# TPA6132A2RTER.net
KiCad netlist of a schematic drawn in EAGLE
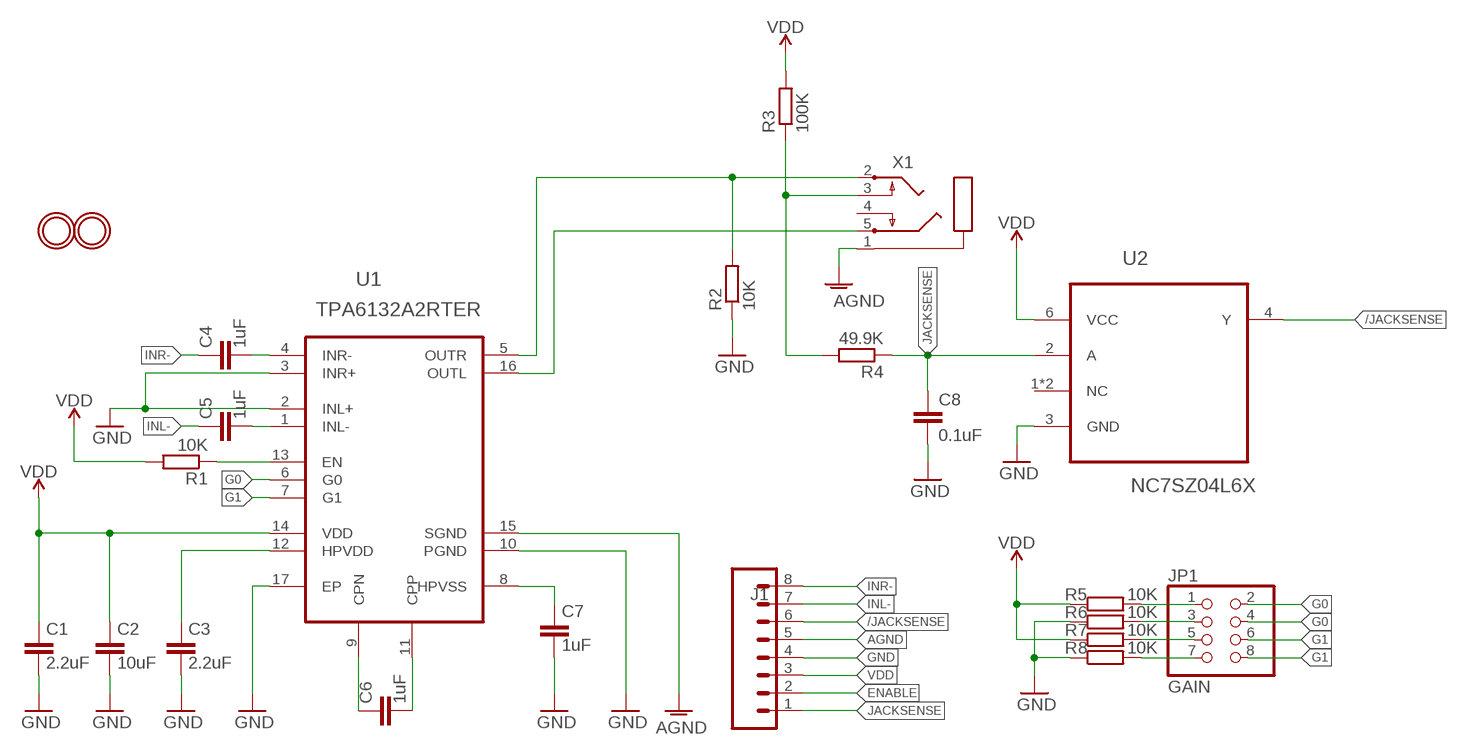
[diagram p0: schematic, sheet 1]

(export (version "E")
  (design (tool "Eeschema 10.0.6"))
  (components
    (comp (ref "C1")
      (value "2.2uF")
      (footprint "eagle-import:C0402K")
      (libsource (lib "eagle-import") (part "C-EUC0402K"))
    )
    (comp (ref "C2")
      (value "10uF")
      (footprint "eagle-import:C0402K")
      (libsource (lib "eagle-import") (part "C-EUC0402K"))
    )
    (comp (ref "C3")
      (value "2.2uF")
      (footprint "eagle-import:C0402K")
      (libsource (lib "eagle-import") (part "C-EUC0402K"))
    )
    (comp (ref "C4")
      (value "1uF")
      (footprint "eagle-import:C0402K")
      (libsource (lib "eagle-import") (part "C-EUC0402K"))
    )
    (comp (ref "C5")
      (value "1uF")
      (footprint "eagle-import:C0402K")
      (libsource (lib "eagle-import") (part "C-EUC0402K"))
    )
    (comp (ref "C6")
      (value "1uF")
      (footprint "eagle-import:C0402K")
      (libsource (lib "eagle-import") (part "C-EUC0402K"))
    )
    (comp (ref "C7")
      (value "1uF")
      (footprint "eagle-import:C0402K")
      (libsource (lib "eagle-import") (part "C-EUC0402K"))
    )
    (comp (ref "C8")
      (value "0.1uF")
      (footprint "eagle-import:C0402K")
      (libsource (lib "eagle-import") (part "C-EUC0402K"))
    )
    (comp (ref "J1")
      (value "CONN_08NO_SILK_FEMALE_PTH")
      (footprint "eagle-import:1X08_NO_SILK")
      (libsource (lib "eagle-import") (part "CONN_08NO_SILK_FEMALE_PTH"))
    )
    (comp (ref "JP1")
      (value "GAIN")
      (footprint "eagle-import:2X04")
      (libsource (lib "eagle-import") (part "PINHD-2X4"))
    )
    (comp (ref "MH1")
      (value "MOUNTINGHOLE2.5")
      (footprint "eagle-import:MOUNTINGHOLE_2.5_PLATED")
      (libsource (lib "eagle-import") (part "MOUNTINGHOLE2.5"))
    )
    (comp (ref "MH2")
      (value "MOUNTINGHOLE2.5")
      (footprint "eagle-import:MOUNTINGHOLE_2.5_PLATED")
      (libsource (lib "eagle-import") (part "MOUNTINGHOLE2.5"))
    )
    (comp (ref "R1")
      (value "10K")
      (footprint "eagle-import:R0402")
      (libsource (lib "eagle-import") (part "R-EU_R0402"))
    )
    (comp (ref "R2")
      (value "10K")
      (footprint "eagle-import:R0402")
      (libsource (lib "eagle-import") (part "R-EU_R0402"))
    )
    (comp (ref "R3")
      (value "100K")
      (footprint "eagle-import:R0402")
      (libsource (lib "eagle-import") (part "R-EU_R0402"))
    )
    (comp (ref "R4")
      (value "49.9K")
      (footprint "eagle-import:R0402")
      (libsource (lib "eagle-import") (part "R-EU_R0402"))
    )
    (comp (ref "R5")
      (value "10K")
      (footprint "eagle-import:R0402")
      (libsource (lib "eagle-import") (part "R-EU_R0402"))
    )
    (comp (ref "R6")
      (value "10K")
      (footprint "eagle-import:R0402")
      (libsource (lib "eagle-import") (part "R-EU_R0402"))
    )
    (comp (ref "R7")
      (value "10K")
      (footprint "eagle-import:R0402")
      (libsource (lib "eagle-import") (part "R-EU_R0402"))
    )
    (comp (ref "R8")
      (value "10K")
      (footprint "eagle-import:R0402")
      (libsource (lib "eagle-import") (part "R-EU_R0402"))
    )
    (comp (ref "U1")
      (value "TPA6132A2RTER")
      (footprint "eagle-import:QFN50P300X300X80-16N")
      (fields (field (name "MF") "Texas Instruments"))
      (libsource (lib "eagle-import") (part "TPA6132A2RTER"))
    )
    (comp (ref "U2")
      (value "NC7SZ04L6X")
      (footprint "eagle-import:MICROPAK-6")
      (libsource (lib "eagle-import") (part "NC7SZ04L6X"))
    )
    (comp (ref "X1")
      (value "STEREOJACKSTX3120-5B")
      (footprint "eagle-import:STX3100")
      (libsource (lib "eagle-import") (part "STEREOJACKSTX3120-5B"))
    )
  )
  (nets
    (net (code "1") (name "AGND") (class "Default")
      (node (ref "J1") (pin "5") (pinfunction "5_5") (pintype "passive"))
      (node (ref "U1") (pin "15") (pinfunction "SGND_15") (pintype "passive"))
      (node (ref "X1") (pin "1") (pinfunction "1_1") (pintype "passive"))
    )
    (net (code "2") (name "ENABLE") (class "Default")
      (node (ref "J1") (pin "2") (pinfunction "2_2") (pintype "passive"))
      (node (ref "R1") (pin "1") (pinfunction "1_1") (pintype "passive"))
      (node (ref "U1") (pin "13") (pinfunction "EN_13") (pintype "input"))
    )
    (net (code "3") (name "G0") (class "Default")
      (node (ref "JP1") (pin "2") (pinfunction "2_2") (pintype "passive"))
      (node (ref "JP1") (pin "4") (pinfunction "4_4") (pintype "passive"))
      (node (ref "U1") (pin "6") (pinfunction "G0_6") (pintype "input"))
    )
    (net (code "4") (name "G1") (class "Default")
      (node (ref "JP1") (pin "6") (pinfunction "6_6") (pintype "passive"))
      (node (ref "JP1") (pin "8") (pinfunction "8_8") (pintype "passive"))
      (node (ref "U1") (pin "7") (pinfunction "G1_7") (pintype "input"))
    )
    (net (code "5") (name "GND") (class "Default")
      (node (ref "C1") (pin "2") (pinfunction "2_2") (pintype "passive"))
      (node (ref "C2") (pin "2") (pinfunction "2_2") (pintype "passive"))
      (node (ref "C3") (pin "2") (pinfunction "2_2") (pintype "passive"))
      (node (ref "C7") (pin "2") (pinfunction "2_2") (pintype "passive"))
      (node (ref "C8") (pin "2") (pinfunction "2_2") (pintype "passive"))
      (node (ref "J1") (pin "4") (pinfunction "4_4") (pintype "passive"))
      (node (ref "R2") (pin "1") (pinfunction "1_1") (pintype "passive"))
      (node (ref "R6") (pin "1") (pinfunction "1_1") (pintype "passive"))
      (node (ref "R8") (pin "1") (pinfunction "1_1") (pintype "passive"))
      (node (ref "U1") (pin "10") (pinfunction "PGND_10") (pintype "passive"))
      (node (ref "U1") (pin "17") (pinfunction "EP_17") (pintype "passive"))
      (node (ref "U1") (pin "2") (pinfunction "INL+_2") (pintype "input"))
      (node (ref "U1") (pin "3") (pinfunction "INR+_3") (pintype "input"))
      (node (ref "U2") (pin "3") (pinfunction "GND_3") (pintype "passive"))
    )
    (net (code "6") (name "INL-") (class "Default")
      (node (ref "C5") (pin "1") (pinfunction "1_1") (pintype "passive"))
      (node (ref "J1") (pin "7") (pinfunction "7_7") (pintype "passive"))
    )
    (net (code "7") (name "INR-") (class "Default")
      (node (ref "C4") (pin "1") (pinfunction "1_1") (pintype "passive"))
      (node (ref "J1") (pin "8") (pinfunction "8_8") (pintype "passive"))
    )
    (net (code "8") (name "JACKSENSE") (class "Default")
      (node (ref "C8") (pin "1") (pinfunction "1_1") (pintype "passive"))
      (node (ref "J1") (pin "1") (pinfunction "1_1") (pintype "passive"))
      (node (ref "R4") (pin "1") (pinfunction "1_1") (pintype "passive"))
      (node (ref "U2") (pin "2") (pinfunction "A_2") (pintype "input"))
    )
    (net (code "9") (name "Net-(JP1-Pad1)") (class "Default")
      (node (ref "JP1") (pin "1") (pinfunction "1_1") (pintype "passive"))
      (node (ref "R5") (pin "2") (pinfunction "2_2") (pintype "passive"))
    )
    (net (code "10") (name "Net-(JP1-Pad3)") (class "Default")
      (node (ref "JP1") (pin "3") (pinfunction "3_3") (pintype "passive"))
      (node (ref "R6") (pin "2") (pinfunction "2_2") (pintype "passive"))
    )
    (net (code "11") (name "Net-(JP1-Pad5)") (class "Default")
      (node (ref "JP1") (pin "5") (pinfunction "5_5") (pintype "passive"))
      (node (ref "R7") (pin "2") (pinfunction "2_2") (pintype "passive"))
    )
    (net (code "12") (name "Net-(JP1-Pad7)") (class "Default")
      (node (ref "JP1") (pin "7") (pinfunction "7_7") (pintype "passive"))
      (node (ref "R8") (pin "2") (pinfunction "2_2") (pintype "passive"))
    )
    (net (code "13") (name "Net-(R3-Pad1)") (class "Default")
      (node (ref "R3") (pin "1") (pinfunction "1_1") (pintype "passive"))
      (node (ref "R4") (pin "2") (pinfunction "2_2") (pintype "passive"))
      (node (ref "X1") (pin "3") (pinfunction "3_3") (pintype "passive"))
    )
    (net (code "14") (name "Net-(U1-CPN)") (class "Default")
      (node (ref "C6") (pin "1") (pinfunction "1_1") (pintype "passive"))
      (node (ref "U1") (pin "9") (pinfunction "CPN_9") (pintype "power_in"))
    )
    (net (code "15") (name "Net-(U1-CPP)") (class "Default")
      (node (ref "C6") (pin "2") (pinfunction "2_2") (pintype "passive"))
      (node (ref "U1") (pin "11") (pinfunction "CPP_11") (pintype "power_in"))
    )
    (net (code "16") (name "Net-(U1-HPVDD)") (class "Default")
      (node (ref "C3") (pin "1") (pinfunction "1_1") (pintype "passive"))
      (node (ref "U1") (pin "12") (pinfunction "HPVDD_12") (pintype "power_in"))
    )
    (net (code "17") (name "Net-(U1-HPVSS)") (class "Default")
      (node (ref "C7") (pin "1") (pinfunction "1_1") (pintype "passive"))
      (node (ref "U1") (pin "8") (pinfunction "HPVSS_8") (pintype "power_in"))
    )
    (net (code "18") (name "Net-(U1-INL-)") (class "Default")
      (node (ref "C5") (pin "2") (pinfunction "2_2") (pintype "passive"))
      (node (ref "U1") (pin "1") (pinfunction "INL-_1") (pintype "input"))
    )
    (net (code "19") (name "Net-(U1-INR-)") (class "Default")
      (node (ref "C4") (pin "2") (pinfunction "2_2") (pintype "passive"))
      (node (ref "U1") (pin "4") (pinfunction "INR-_4") (pintype "input"))
    )
    (net (code "20") (name "Net-(U1-OUTL)") (class "Default")
      (node (ref "U1") (pin "16") (pinfunction "OUTL_16") (pintype "output"))
      (node (ref "X1") (pin "5") (pinfunction "5_5") (pintype "passive"))
    )
    (net (code "21") (name "Net-(U1-OUTR)") (class "Default")
      (node (ref "R2") (pin "2") (pinfunction "2_2") (pintype "passive"))
      (node (ref "U1") (pin "5") (pinfunction "OUTR_5") (pintype "output"))
      (node (ref "X1") (pin "2") (pinfunction "2_2") (pintype "passive"))
    )
    (net (code "22") (name "VDD") (class "Default")
      (node (ref "C1") (pin "1") (pinfunction "1_1") (pintype "passive"))
      (node (ref "C2") (pin "1") (pinfunction "1_1") (pintype "passive"))
      (node (ref "J1") (pin "3") (pinfunction "3_3") (pintype "passive"))
      (node (ref "R1") (pin "2") (pinfunction "2_2") (pintype "passive"))
      (node (ref "R3") (pin "2") (pinfunction "2_2") (pintype "passive"))
      (node (ref "R5") (pin "1") (pinfunction "1_1") (pintype "passive"))
      (node (ref "R7") (pin "1") (pinfunction "1_1") (pintype "passive"))
      (node (ref "U1") (pin "14") (pinfunction "VDD_14") (pintype "power_in"))
      (node (ref "U2") (pin "6") (pinfunction "VCC_6") (pintype "power_in"))
    )
    (net (code "23") (name "unconnected-(U2-NC-Pad1)") (class "Default")
      (node (ref "U2") (pin "1") (pinfunction "NC_1") (pintype "no_connect"))
    )
    (net (code "24") (name "unconnected-(U2-NC-Pad5)") (class "Default")
      (node (ref "U2") (pin "5") (pinfunction "NC_5") (pintype "no_connect"))
    )
    (net (code "25") (name "unconnected-(X1-Pad4)") (class "Default")
      (node (ref "X1") (pin "4") (pinfunction "4_4") (pintype "passive"))
    )
    (net (code "26") (name "{slash}JACKSENSE") (class "Default")
      (node (ref "J1") (pin "6") (pinfunction "6_6") (pintype "passive"))
      (node (ref "U2") (pin "4") (pinfunction "Y_4") (pintype "output"))
    )
  )
)
